# Display.net
KiCad netlist of a schematic drawn in Altium Designer
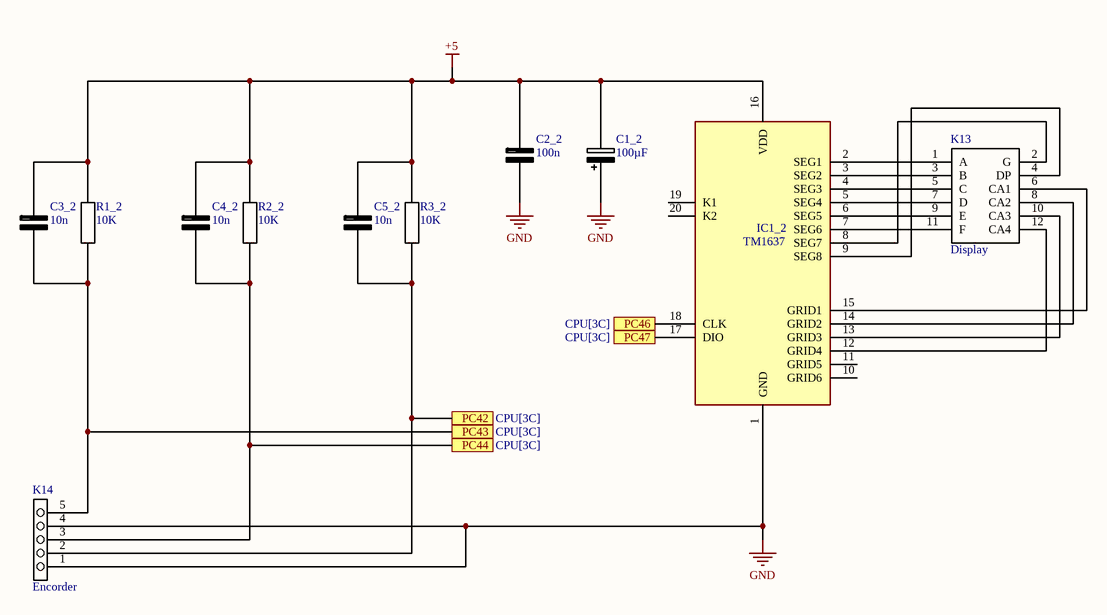
[diagram p0: Display.SchDoc]

(export (version "E")
  (design (tool "Eeschema 10.0.6"))
  (components
    (comp (ref "C1_2")
      (value "100µF")
      (footprint "SamacSys:CAPPRD350W60D825H1300")
      (description "Capacitor Polarised")
      (fields (field (name "MANUFACTURER_PART_NUMBER") "RGA101M1HBK-0811G"))
      (libsource (lib "SamacSys") (part "RGA101M1HBK-0811G"))
    )
    (comp (ref "C2_2")
      (value "100n")
      (footprint "0805")
      (description "Capacitor")
      (fields (field (name "MANUFACTURER_PART_NUMBER") "C0805C391G3GACTU"))
      (libsource (lib "SamacSys") (part "0805 (Capacitor)"))
    )
    (comp (ref "C3_2")
      (value "10n")
      (footprint "0805")
      (description "Capacitor")
      (fields (field (name "MANUFACTURER_PART_NUMBER") "C0805C391G3GACTU"))
      (libsource (lib "SamacSys") (part "0805 (Capacitor)"))
    )
    (comp (ref "C4_2")
      (value "10n")
      (footprint "0805")
      (description "Capacitor")
      (fields (field (name "MANUFACTURER_PART_NUMBER") "C0805C391G3GACTU"))
      (libsource (lib "SamacSys") (part "0805 (Capacitor)"))
    )
    (comp (ref "C5_2")
      (value "10n")
      (footprint "0805")
      (description "Capacitor")
      (fields (field (name "MANUFACTURER_PART_NUMBER") "C0805C391G3GACTU"))
      (libsource (lib "SamacSys") (part "0805 (Capacitor)"))
    )
    (comp (ref "IC1_2")
      (value "TM1637")
      (footprint "SamacSys:tm1637")
      (description "Integrated Circuit")
      (fields (field (name "MANUFACTURER_PART_NUMBER") "TM1637 (SOP)"))
      (libsource (lib "SamacSys") (part "TM1637__SOP_"))
    )
    (comp (ref "K13")
      (value "Display")
      (footprint "SamacSys:HDRV12W64P254_2X6_1524X508X909P")
      (description "Connector 12-PIN")
      (fields (field (name "MANUFACTURER_PART_NUMBER") "240-062"))
      (libsource (lib "SamacSys") (part "240-062"))
    )
    (comp (ref "K14")
      (value "Encorder")
      (footprint "SamacSys:HDRV5W64P0X254_1X5_1270X254X864P")
      (description "Connector 5-PIN")
      (fields
        (field (name "MOUSER2 PART NUMBER") "855-M20-9990545")
        (field (name "MANUFACTURER_PART_NUMBER") "M20-9990545")
      )
      (libsource (lib "SamacSys") (part "M20-9990545"))
    )
    (comp (ref "R1_2")
      (value "10K")
      (footprint "0805")
      (description "Resistor")
      (fields (field (name "MANUFACTURER_PART_NUMBER") "C0805C391G3GACTU"))
      (libsource (lib "SamacSys") (part "0805 (Resistor)"))
    )
    (comp (ref "R2_2")
      (value "10K")
      (footprint "0805")
      (description "Resistor")
      (fields (field (name "MANUFACTURER_PART_NUMBER") "C0805C391G3GACTU"))
      (libsource (lib "SamacSys") (part "0805 (Resistor)"))
    )
    (comp (ref "R3_2")
      (value "10K")
      (footprint "0805")
      (description "Resistor")
      (fields (field (name "MANUFACTURER_PART_NUMBER") "C0805C391G3GACTU"))
      (libsource (lib "SamacSys") (part "0805 (Resistor)"))
    )
  )
  (nets
    (net (code "1") (name "+5") (class "Default")
      (node (ref "C1_2") (pin "2") (pinfunction "-_2") (pintype "passive"))
      (node (ref "C2_2") (pin "2") (pinfunction "-_2") (pintype "passive"))
      (node (ref "C3_2") (pin "2") (pinfunction "-_2") (pintype "passive"))
      (node (ref "C4_2") (pin "2") (pinfunction "-_2") (pintype "passive"))
      (node (ref "C5_2") (pin "2") (pinfunction "-_2") (pintype "passive"))
      (node (ref "IC1_2") (pin "16") (pinfunction "VDD_16") (pintype "passive"))
      (node (ref "R1_2") (pin "2") (pinfunction "2_2") (pintype "passive"))
      (node (ref "R2_2") (pin "2") (pinfunction "2_2") (pintype "passive"))
      (node (ref "R3_2") (pin "2") (pinfunction "2_2") (pintype "passive"))
    )
    (net (code "2") (name "/PC42") (class "Default")
      (node (ref "C5_2") (pin "1") (pinfunction "+_1") (pintype "passive"))
      (node (ref "K14") (pin "2") (pinfunction "2_2") (pintype "passive"))
      (node (ref "R3_2") (pin "1") (pinfunction "1_1") (pintype "passive"))
    )
    (net (code "3") (name "/PC43") (class "Default")
      (node (ref "C3_2") (pin "1") (pinfunction "+_1") (pintype "passive"))
      (node (ref "K14") (pin "5") (pinfunction "5_5") (pintype "passive"))
      (node (ref "R1_2") (pin "1") (pinfunction "1_1") (pintype "passive"))
    )
    (net (code "4") (name "/PC44") (class "Default")
      (node (ref "C4_2") (pin "1") (pinfunction "+_1") (pintype "passive"))
      (node (ref "K14") (pin "3") (pinfunction "3_3") (pintype "passive"))
      (node (ref "R2_2") (pin "1") (pinfunction "1_1") (pintype "passive"))
    )
    (net (code "5") (name "/PC46") (class "Default")
      (node (ref "IC1_2") (pin "18") (pinfunction "CLK_18") (pintype "passive"))
    )
    (net (code "6") (name "/PC47") (class "Default")
      (node (ref "IC1_2") (pin "17") (pinfunction "DIO_17") (pintype "passive"))
    )
    (net (code "7") (name "GND") (class "Default")
      (node (ref "C1_2") (pin "1") (pinfunction "+_1") (pintype "passive"))
      (node (ref "C2_2") (pin "1") (pinfunction "+_1") (pintype "passive"))
      (node (ref "IC1_2") (pin "1") (pinfunction "GND_1") (pintype "passive"))
      (node (ref "K14") (pin "1") (pinfunction "1_1") (pintype "passive"))
      (node (ref "K14") (pin "4") (pinfunction "4_4") (pintype "passive"))
    )
    (net (code "8") (name "Net-(IC1_2-GRID1)") (class "Default")
      (node (ref "IC1_2") (pin "15") (pinfunction "GRID1_15") (pintype "passive"))
      (node (ref "K13") (pin "6") (pinfunction "CA1_6") (pintype "passive"))
    )
    (net (code "9") (name "Net-(IC1_2-GRID2)") (class "Default")
      (node (ref "IC1_2") (pin "14") (pinfunction "GRID2_14") (pintype "passive"))
      (node (ref "K13") (pin "8") (pinfunction "CA2_8") (pintype "passive"))
    )
    (net (code "10") (name "Net-(IC1_2-GRID3)") (class "Default")
      (node (ref "IC1_2") (pin "13") (pinfunction "GRID3_13") (pintype "passive"))
      (node (ref "K13") (pin "10") (pinfunction "CA3_10") (pintype "passive"))
    )
    (net (code "11") (name "Net-(IC1_2-GRID4)") (class "Default")
      (node (ref "IC1_2") (pin "12") (pinfunction "GRID4_12") (pintype "passive"))
      (node (ref "K13") (pin "12") (pinfunction "CA4_12") (pintype "passive"))
    )
    (net (code "12") (name "Net-(IC1_2-SEG1)") (class "Default")
      (node (ref "IC1_2") (pin "2") (pinfunction "SEG1_2") (pintype "passive"))
      (node (ref "K13") (pin "1") (pinfunction "A_1") (pintype "passive"))
    )
    (net (code "13") (name "Net-(IC1_2-SEG2)") (class "Default")
      (node (ref "IC1_2") (pin "3") (pinfunction "SEG2_3") (pintype "passive"))
      (node (ref "K13") (pin "3") (pinfunction "B_3") (pintype "passive"))
    )
    (net (code "14") (name "Net-(IC1_2-SEG3)") (class "Default")
      (node (ref "IC1_2") (pin "4") (pinfunction "SEG3_4") (pintype "passive"))
      (node (ref "K13") (pin "5") (pinfunction "C_5") (pintype "passive"))
    )
    (net (code "15") (name "Net-(IC1_2-SEG4)") (class "Default")
      (node (ref "IC1_2") (pin "5") (pinfunction "SEG4_5") (pintype "passive"))
      (node (ref "K13") (pin "7") (pinfunction "D_7") (pintype "passive"))
    )
    (net (code "16") (name "Net-(IC1_2-SEG5)") (class "Default")
      (node (ref "IC1_2") (pin "6") (pinfunction "SEG5_6") (pintype "passive"))
      (node (ref "K13") (pin "9") (pinfunction "E_9") (pintype "passive"))
    )
    (net (code "17") (name "Net-(IC1_2-SEG6)") (class "Default")
      (node (ref "IC1_2") (pin "7") (pinfunction "SEG6_7") (pintype "passive"))
      (node (ref "K13") (pin "11") (pinfunction "F_11") (pintype "passive"))
    )
    (net (code "18") (name "Net-(IC1_2-SEG7)") (class "Default")
      (node (ref "IC1_2") (pin "8") (pinfunction "SEG7_8") (pintype "passive"))
      (node (ref "K13") (pin "2") (pinfunction "G_2") (pintype "passive"))
    )
    (net (code "19") (name "Net-(IC1_2-SEG8)") (class "Default")
      (node (ref "IC1_2") (pin "9") (pinfunction "SEG8_9") (pintype "passive"))
      (node (ref "K13") (pin "4") (pinfunction "DP_4") (pintype "passive"))
    )
    (net (code "20") (name "unconnected-(IC1_2-GRID5-Pad11)") (class "Default")
      (node (ref "IC1_2") (pin "11") (pinfunction "GRID5_11") (pintype "passive"))
    )
    (net (code "21") (name "unconnected-(IC1_2-GRID6-Pad10)") (class "Default")
      (node (ref "IC1_2") (pin "10") (pinfunction "GRID6_10") (pintype "passive"))
    )
    (net (code "22") (name "unconnected-(IC1_2-K1-Pad19)") (class "Default")
      (node (ref "IC1_2") (pin "19") (pinfunction "K1_19") (pintype "passive"))
    )
    (net (code "23") (name "unconnected-(IC1_2-K2-Pad20)") (class "Default")
      (node (ref "IC1_2") (pin "20") (pinfunction "K2_20") (pintype "passive"))
    )
  )
)
